# MAIN.net
KiCad netlist of a schematic drawn in Altium Designer
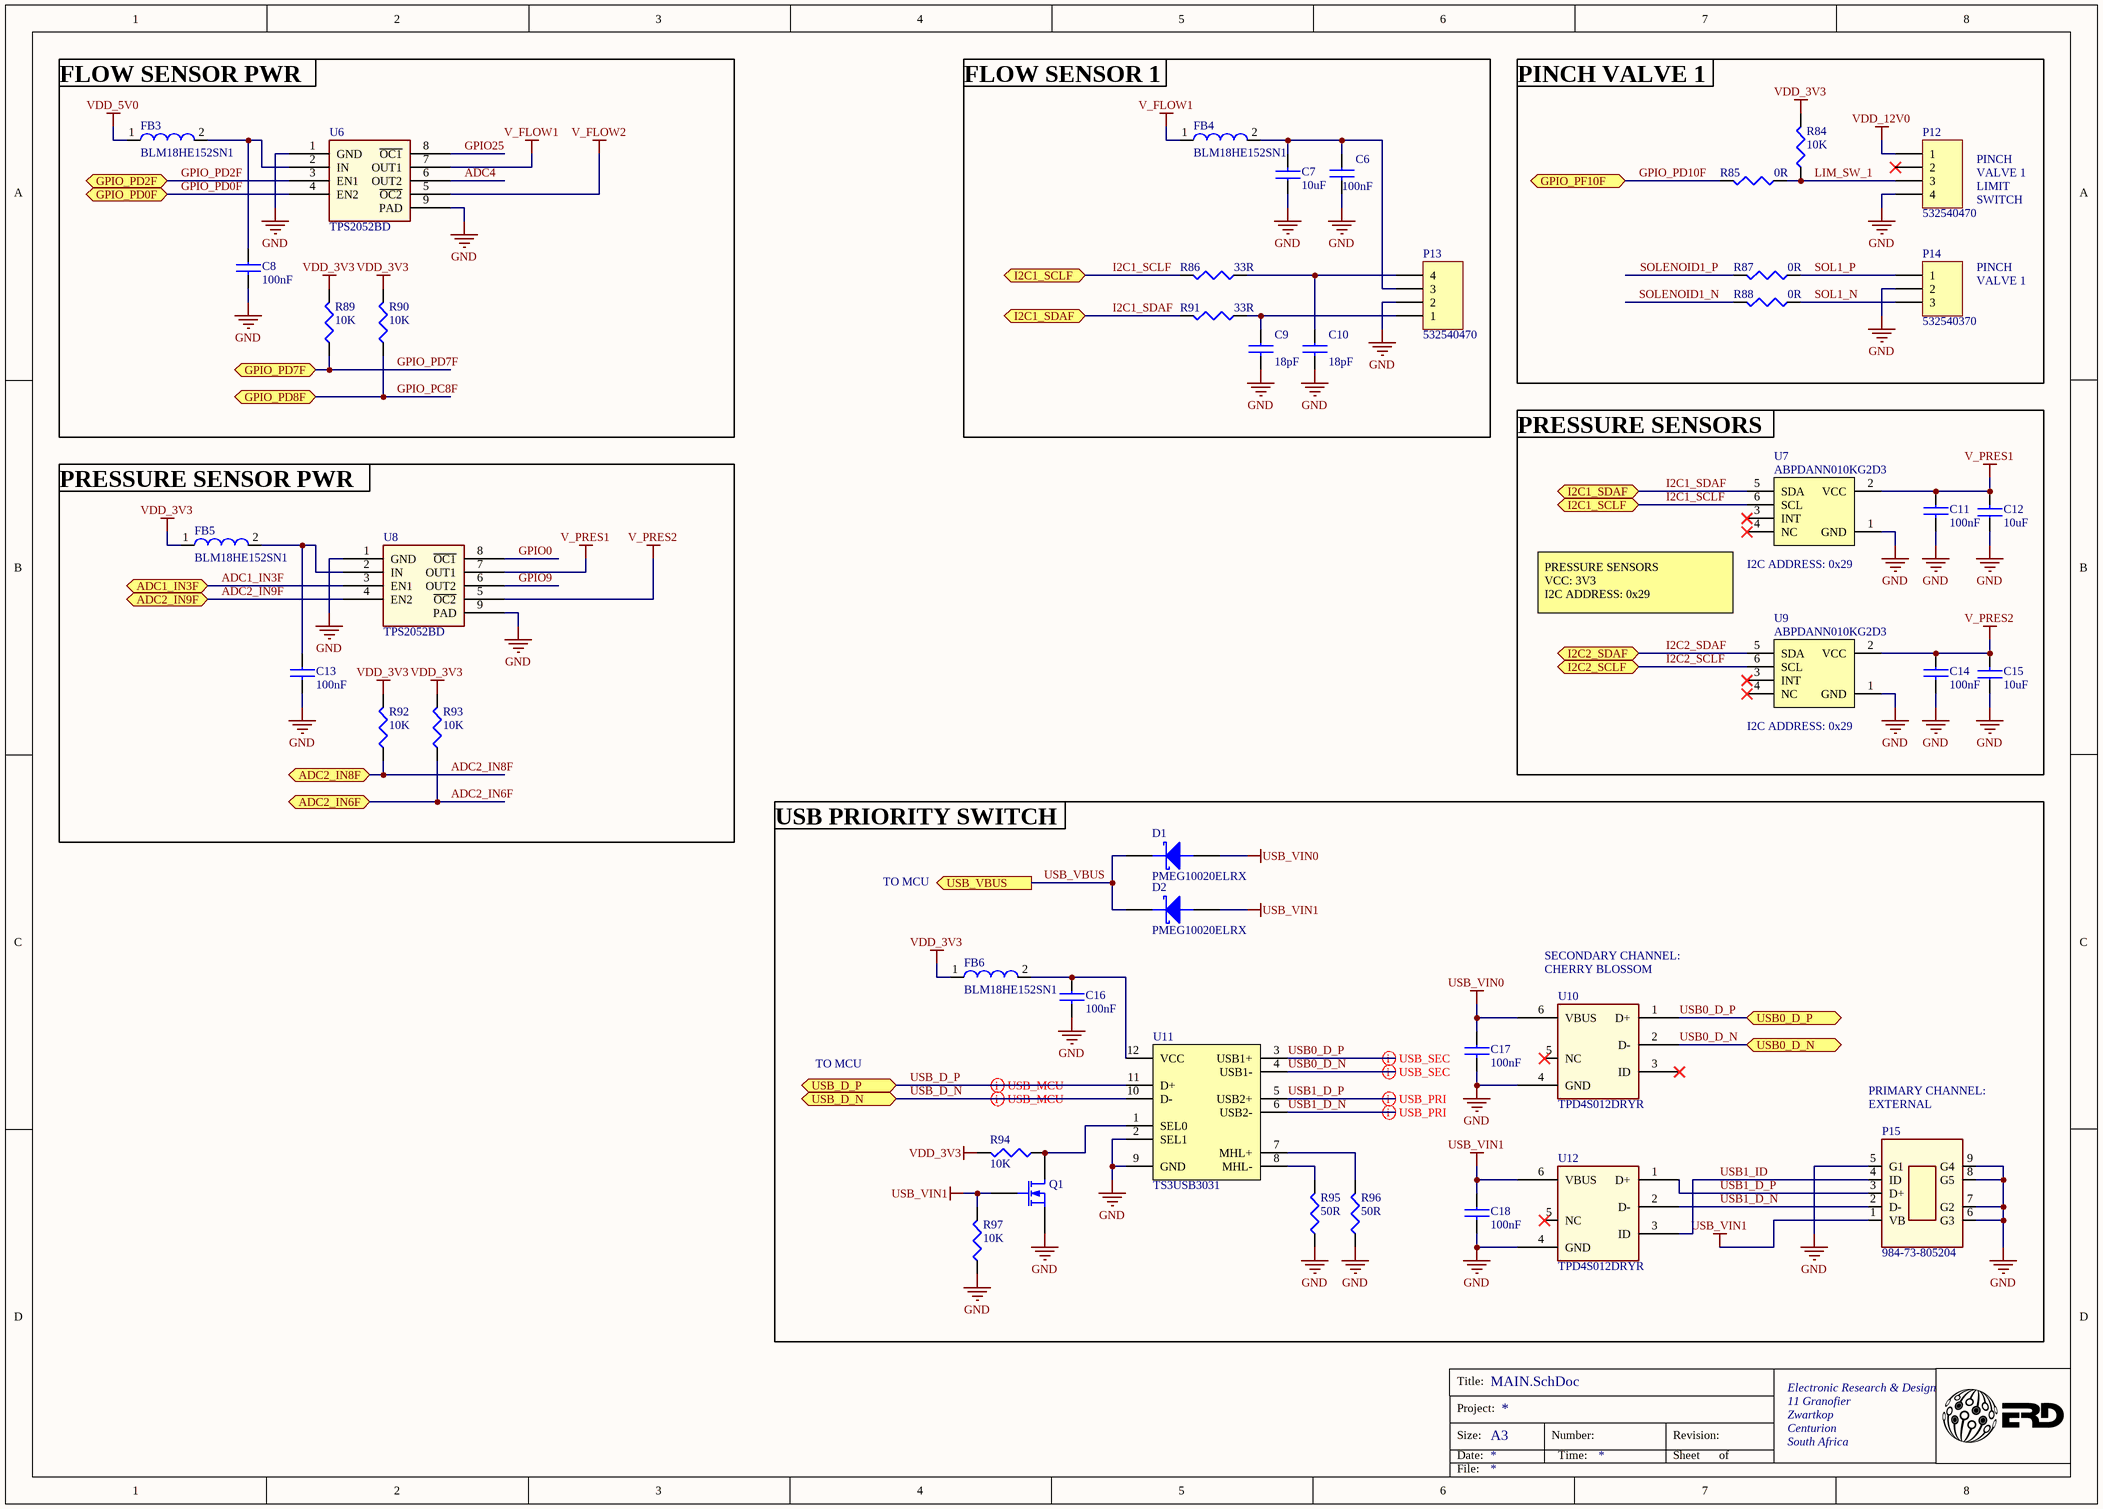
[diagram p0: MAIN.SchDoc]

(export (version "E")
  (design (tool "Eeschema 10.0.6"))
  (components
    (comp (ref "C6")
      (value "100nF")
      (footprint "CC0402")
      (description "CAP CER 0.1UF 50V 10% X7R 0402")
      (fields (field (name "MANUFACTURER") "Murata") (field (name "PART NUMBER") "GCM155R71H104KE02D"))
      (libsource (lib "ERD TiAm") (part "CAP CER 0.1UF 10V 10% X5R 0402"))
    )
    (comp (ref "C7")
      (value "10uF")
      (footprint "CC0603")
      (description "CAP CER 10UF 25V 20% X5R 0603")
      (fields (field (name "MANUFACTURER") "Murata") (field (name "PARTNUMBER") "GRM188R61E106MA73D"))
      (libsource (lib "ERD TiAm") (part "CAP CER 0.1UF 10V 10% X5R 0402"))
    )
    (comp (ref "C8")
      (value "100nF")
      (footprint "CC0402")
      (description "CAP CER 0.1UF 50V 10% X7R 0402")
      (fields (field (name "MANUFACTURER") "Murata") (field (name "PARTNUMBER") "GCM155R71H104KE02D"))
      (libsource (lib "ERD TiAm") (part "CAP CER 0.1UF 10V 10% X5R 0402"))
    )
    (comp (ref "C9")
      (value "18pF")
      (footprint "CC0402")
      (description "CAP CER 18pF 50V 5% C0G 0402")
      (fields (field (name "MANUFACTURER") "AVX") (field (name "PARTNUMBER") "GJM1555C1H180FB01D"))
      (libsource (lib "ERD TiAm") (part "CAP CER 2.2UF 6.3V 10% X5R 0402"))
    )
    (comp (ref "C10")
      (value "18pF")
      (footprint "CC0402")
      (description "CAP CER 18pF 50V 5% C0G 0402")
      (fields (field (name "MANUFACTURER") "AVX") (field (name "PARTNUMBER") "GJM1555C1H180FB01D"))
      (libsource (lib "ERD TiAm") (part "CAP CER 2.2UF 6.3V 10% X5R 0402"))
    )
    (comp (ref "C11")
      (value "100nF")
      (footprint "CC0402")
      (description "CAP CER 0.1UF 50V 10% X7R 0402")
      (fields (field (name "MANUFACTURER") "Murata") (field (name "PARTNUMBER") "GCM155R71H104KE02D"))
      (libsource (lib "ERD TiAm") (part "CAP CER 0.1UF 10V 10% X5R 0402"))
    )
    (comp (ref "C12")
      (value "10uF")
      (footprint "CC0603")
      (description "CAP CER 10UF 25V 20% X5R 0603")
      (fields (field (name "MANUFACTURER") "Murata") (field (name "PARTNUMBER") "GRM188R61E106MA73D"))
      (libsource (lib "ERD TiAm") (part "CAP CER 0.1UF 10V 10% X5R 0402"))
    )
    (comp (ref "C13")
      (value "100nF")
      (footprint "CC0402")
      (description "CAP CER 0.1UF 50V 10% X7R 0402")
      (fields (field (name "MANUFACTURER") "Murata") (field (name "PARTNUMBER") "GCM155R71H104KE02D"))
      (libsource (lib "ERD TiAm") (part "CAP CER 0.1UF 10V 10% X5R 0402"))
    )
    (comp (ref "C14")
      (value "100nF")
      (footprint "CC0402")
      (description "CAP CER 0.1UF 50V 10% X7R 0402")
      (fields (field (name "MANUFACTURER") "Murata") (field (name "PARTNUMBER") "GCM155R71H104KE02D"))
      (libsource (lib "ERD TiAm") (part "CAP CER 0.1UF 10V 10% X5R 0402"))
    )
    (comp (ref "C15")
      (value "10uF")
      (footprint "CC0603")
      (description "CAP CER 10UF 25V 20% X5R 0603")
      (fields (field (name "MANUFACTURER") "Murata") (field (name "PARTNUMBER") "GRM188R61E106MA73D"))
      (libsource (lib "ERD TiAm") (part "CAP CER 0.1UF 10V 10% X5R 0402"))
    )
    (comp (ref "C16")
      (value "100nF")
      (footprint "CC0402")
      (description "CAP CER 0.1UF 50V 10% X7R 0402")
      (fields (field (name "MANUFACTURER") "Murata") (field (name "PARTNUMBER") "GCM155R71H104KE02D"))
      (libsource (lib "ERD TiAm") (part "CAP CER 0.1UF 10V 10% X5R 0402"))
    )
    (comp (ref "C17")
      (value "100nF")
      (footprint "CC0402")
      (description "CAP CER 0.1UF 50V 10% X7R 0402")
      (fields (field (name "MANUFACTURER") "Murata") (field (name "PARTNUMBER") "GCM155R71H104KE02D"))
      (libsource (lib "ERD TiAm") (part "CAP CER 0.1UF 10V 10% X5R 0402"))
    )
    (comp (ref "C18")
      (value "100nF")
      (footprint "CC0402")
      (description "CAP CER 0.1UF 50V 10% X7R 0402")
      (fields (field (name "MANUFACTURER") "Murata") (field (name "PARTNUMBER") "GCM155R71H104KE02D"))
      (libsource (lib "ERD TiAm") (part "CAP CER 0.1UF 10V 10% X5R 0402"))
    )
    (comp (ref "D1")
      (value "PMEG10020ELRX")
      (footprint "SOD123W")
      (description "DIODE, SCHOTTKY, 100V, 2A, 3.7ns, SOD123W")
      (libsource (lib "GadgetJD") (part "DIODE SCHOTTKY"))
    )
    (comp (ref "D2")
      (value "PMEG10020ELRX")
      (footprint "SOD123W")
      (description "DIODE, SCHOTTKY, 100V, 2A, 3.7ns, SOD123W")
      (libsource (lib "GadgetJD") (part "DIODE SCHOTTKY"))
    )
    (comp (ref "FB3")
      (value "BLM18HE152SN1")
      (footprint "LC0603")
      (description "FERRITE, 500mA, 500mOHM, 0603")
      (libsource (lib "BEAGLEBONEBLACK_REV A5B") (part "FER_180_200_0"))
    )
    (comp (ref "FB4")
      (value "BLM18HE152SN1")
      (footprint "LC0603")
      (description "FERRITE, 500mA, 500mOHM, 0603")
      (libsource (lib "BEAGLEBONEBLACK_REV A5B") (part "FER_180_200_0"))
    )
    (comp (ref "FB5")
      (value "BLM18HE152SN1")
      (footprint "LC0603")
      (description "FERRITE, 500mA, 500mOHM, 0603")
      (libsource (lib "BEAGLEBONEBLACK_REV A5B") (part "FER_180_200_0"))
    )
    (comp (ref "FB6")
      (value "BLM18HE152SN1")
      (footprint "LC0603")
      (description "FERRITE, 500mA, 500mOHM, 0603")
      (libsource (lib "BEAGLEBONEBLACK_REV A5B") (part "FER_180_200_0"))
    )
    (comp (ref "P12")
      (value "532540470")
      (footprint "HDR1X4")
      (description "Header, RA, 4-circuit, 2mm pitch, TH")
      (fields (field (name "MANUFACTURER") "Molex"))
      (libsource (lib "") (part "Header 4_1"))
    )
    (comp (ref "P13")
      (value "532540470")
      (footprint "HDR1X4")
      (description "Header, RA, 4-circuit, 2mm pitch, TH")
      (fields (field (name "MANUFACTURER") "Molex"))
      (libsource (lib "Miscellaneous Connectors") (part "Header 4"))
    )
    (comp (ref "P14")
      (value "532540370")
      (footprint "HDR1X3")
      (description "Header, RA, 3-circuit, 2mm pitch, TH")
      (fields (field (name "MANUFACTURER") "Molex"))
      (libsource (lib "Miscellaneous Connectors") (part "Header 3"))
    )
    (comp (ref "P15")
      (value "984-73-805204")
      (footprint "984-73-805204")
      (description "CONN RCPT USB MICRO B R/A SMD")
      (fields (field (name "MANUFACTURER") "Pinrex"))
      (libsource (lib "ERD TiAm") (part "MINI-USB-AB-SOCKET"))
    )
    (comp (ref "Q1")
      (value "PMV45EN2R")
      (footprint "SOT23")
      (description "N-Channel FET, 20V, 1.5A, 140mOhm, SOT23")
      (fields (field (name "PUBLISHER") "Altium Limited"))
      (libsource (lib "Miscellaneous Devices") (part "MOSFET-N"))
    )
    (comp (ref "R84")
      (value "10K")
      (footprint "RC0402")
      (description "RES, 10K OHM, 1/16W, 1%, 0402")
      (fields (field (name "MANUFACTURER") "Yageo") (field (name "PART NUMBER") "RC0402FR-0710KL"))
      (libsource (lib "ERD TiAm") (part "RES_10K_1/16W_1%_0402"))
    )
    (comp (ref "R85")
      (value "0R")
      (footprint "RC0402")
      (description "RES, 0 OHM, 1/16W, 1%, 0402")
      (fields (field (name "MANUFACTURER") "Yageo") (field (name "PARTNUMBER") "RC0402FR-070RL"))
      (libsource (lib "ERD TiAm") (part "RES_10K_1/16W_1%_0402"))
    )
    (comp (ref "R86")
      (value "33R")
      (footprint "RC0402")
      (description "RES, 33 OHM, 1/16W, 1%, 0402")
      (fields (field (name "MANUFACTURER") "Yageo") (field (name "PARTNUMBER") "RC0402FR-0733RL"))
      (libsource (lib "ERD TiAm") (part "RES_10K_1/16W_1%_0402"))
    )
    (comp (ref "R87")
      (value "0R")
      (footprint "RC0402")
      (description "RES, 0 OHM, 1/16W, 1%, 0402")
      (fields (field (name "MANUFACTURER") "Yageo") (field (name "PARTNUMBER") "RC0402FR-070RL"))
      (libsource (lib "ERD TiAm") (part "RES_10K_1/16W_1%_0402"))
    )
    (comp (ref "R88")
      (value "0R")
      (footprint "RC0402")
      (description "RES, 0 OHM, 1/16W, 1%, 0402")
      (fields (field (name "MANUFACTURER") "Yageo") (field (name "PARTNUMBER") "RC0402FR-070RL"))
      (libsource (lib "ERD TiAm") (part "RES_10K_1/16W_1%_0402"))
    )
    (comp (ref "R89")
      (value "10K")
      (footprint "RC0402")
      (description "RES, 10K OHM, 1/16W, 1%, 0402")
      (fields (field (name "MANUFACTURER") "Yageo") (field (name "PARTNUMBER") "RC0402FR-0710KL"))
      (libsource (lib "ERD TiAm") (part "RES_10K_1/16W_1%_0402"))
    )
    (comp (ref "R90")
      (value "10K")
      (footprint "RC0402")
      (description "RES, 10K OHM, 1/16W, 1%, 0402")
      (fields (field (name "MANUFACTURER") "Yageo") (field (name "PARTNUMBER") "RC0402FR-0710KL"))
      (libsource (lib "ERD TiAm") (part "RES_10K_1/16W_1%_0402"))
    )
    (comp (ref "R91")
      (value "33R")
      (footprint "RC0402")
      (description "RES, 33 OHM, 1/16W, 1%, 0402")
      (fields (field (name "MANUFACTURER") "Yageo") (field (name "PARTNUMBER") "RC0402FR-0733RL"))
      (libsource (lib "ERD TiAm") (part "RES_10K_1/16W_1%_0402"))
    )
    (comp (ref "R92")
      (value "10K")
      (footprint "RC0402")
      (description "RES, 10K OHM, 1/16W, 1%, 0402")
      (fields (field (name "MANUFACTURER") "Yageo") (field (name "PARTNUMBER") "RC0402FR-0710KL"))
      (libsource (lib "ERD TiAm") (part "RES_10K_1/16W_1%_0402"))
    )
    (comp (ref "R93")
      (value "10K")
      (footprint "RC0402")
      (description "RES, 10K OHM, 1/16W, 1%, 0402")
      (fields (field (name "MANUFACTURER") "Yageo") (field (name "PARTNUMBER") "RC0402FR-0710KL"))
      (libsource (lib "ERD TiAm") (part "RES_10K_1/16W_1%_0402"))
    )
    (comp (ref "R94")
      (value "10K")
      (footprint "RC0402")
      (description "RES, 10K OHM, 1/16W, 1%, 0402")
      (fields (field (name "MANUFACTURER") "Yageo") (field (name "PARTNUMBER") "RC0402FR-0710KL"))
      (libsource (lib "ERD TiAm") (part "RES_10K_1/16W_1%_0402"))
    )
    (comp (ref "R95")
      (value "50R")
      (footprint "RC0402")
      (description "RES, 50 OHM, 1/16W, 1%, 0402")
      (fields (field (name "MANUFACTURER") "Yageo") (field (name "PARTNUMBER") "RC0402FR-0749R9L"))
      (libsource (lib "ERD TiAm") (part "RES_10K_1/16W_1%_0402"))
    )
    (comp (ref "R96")
      (value "50R")
      (footprint "RC0402")
      (description "RES, 50 OHM, 1/16W, 1%, 0402")
      (fields (field (name "MANUFACTURER") "Yageo") (field (name "PARTNUMBER") "RC0402FR-0749R9L"))
      (libsource (lib "ERD TiAm") (part "RES_10K_1/16W_1%_0402"))
    )
    (comp (ref "R97")
      (value "10K")
      (footprint "RC0402")
      (description "RES, 10K OHM, 1/16W, 1%, 0402")
      (fields (field (name "MANUFACTURER") "Yageo") (field (name "PARTNUMBER") "RC0402FR-0710KL"))
      (libsource (lib "ERD TiAm") (part "RES_10K_1/16W_1%_0402"))
    )
    (comp (ref "U6")
      (value "TPS2052BD")
      (description "IC 0.7A PWR DIST SWITCH 8-MSOP")
      (fields (field (name "ALTPARTNUMBER") "MP6231DH"))
      (libsource (lib "BaseBoard") (part "TPS2052"))
    )
    (comp (ref "U7")
      (value "ABPDANN010KG2D3")
      (description "Pressure Sensor, APB Series, TH")
      (libsource (lib "ERD TiAm") (part "ABPDANN010KG2D3"))
    )
    (comp (ref "U8")
      (value "TPS2052BD")
      (description "IC 0.7A PWR DIST SWITCH 8-MSOP")
      (fields (field (name "ALTPARTNUMBER") "MP6231DH"))
      (libsource (lib "BaseBoard") (part "TPS2052"))
    )
    (comp (ref "U9")
      (value "ABPDANN010KG2D3")
      (description "Pressure Sensor, APB Series, TH")
      (libsource (lib "ERD TiAm") (part "ABPDANN010KG2D3"))
    )
    (comp (ref "U10")
      (value "TPD4S012DRYR")
      (footprint "U_6_DRY")
      (description "ESD 4channel USB Interface")
      (fields (field (name "MANUFACTURER") "Texas Instruments"))
      (libsource (lib "ERD TiAm") (part "PROT_TPD4S012"))
    )
    (comp (ref "U11")
      (value "TS3USB3031")
      (description "USB Switch, USB 2.0, VQFN-12")
      (libsource (lib "ERD TiAm") (part "TS3USB3031"))
    )
    (comp (ref "U12")
      (value "TPD4S012DRYR")
      (footprint "U_6_DRY")
      (description "ESD 4channel USB Interface")
      (fields (field (name "MANUFACTURER") "Texas Instruments"))
      (libsource (lib "ERD TiAm") (part "PROT_TPD4S012"))
    )
  )
  (nets
    (net (code "1") (name "/ADC1_IN3F") (class "Default")
      (node (ref "U8") (pin "3") (pinfunction "EN1_3") (pintype "passive"))
    )
    (net (code "2") (name "/ADC2_IN6F") (class "Default")
      (node (ref "R93") (pin "1") (pinfunction "1_1") (pintype "passive"))
    )
    (net (code "3") (name "/ADC2_IN8F") (class "Default")
      (node (ref "R92") (pin "1") (pinfunction "1_1") (pintype "passive"))
    )
    (net (code "4") (name "/ADC2_IN9F") (class "Default")
      (node (ref "U8") (pin "4") (pinfunction "EN2_4") (pintype "passive"))
    )
    (net (code "5") (name "/ADC4") (class "Default")
      (node (ref "U6") (pin "6") (pinfunction "OUT2_6") (pintype "power_in"))
    )
    (net (code "6") (name "/GPIO0") (class "Default")
      (node (ref "U8") (pin "8") (pinfunction "~{OC1}_8") (pintype "power_in"))
    )
    (net (code "7") (name "/GPIO9") (class "Default")
      (node (ref "U8") (pin "6") (pinfunction "OUT2_6") (pintype "power_in"))
    )
    (net (code "8") (name "/GPIO25") (class "Default")
      (node (ref "U6") (pin "8") (pinfunction "~{OC1}_8") (pintype "power_in"))
    )
    (net (code "9") (name "/GPIO_PC8F") (class "Default")
      (node (ref "R90") (pin "1") (pinfunction "1_1") (pintype "passive"))
    )
    (net (code "10") (name "/GPIO_PD0F") (class "Default")
      (node (ref "U6") (pin "4") (pinfunction "EN2_4") (pintype "passive"))
    )
    (net (code "11") (name "/GPIO_PD2F") (class "Default")
      (node (ref "U6") (pin "3") (pinfunction "EN1_3") (pintype "passive"))
    )
    (net (code "12") (name "/GPIO_PD7F") (class "Default")
      (node (ref "R89") (pin "1") (pinfunction "1_1") (pintype "passive"))
    )
    (net (code "13") (name "/GPIO_PD10F") (class "Default")
      (node (ref "R85") (pin "2") (pinfunction "2_2") (pintype "passive"))
    )
    (net (code "14") (name "/I2C1_SCLF") (class "Default")
      (node (ref "R86") (pin "2") (pinfunction "2_2") (pintype "passive"))
      (node (ref "U7") (pin "6") (pinfunction "SCL_6") (pintype "passive"))
    )
    (net (code "15") (name "/I2C1_SDAF") (class "Default")
      (node (ref "R91") (pin "2") (pinfunction "2_2") (pintype "passive"))
      (node (ref "U7") (pin "5") (pinfunction "SDA_5") (pintype "passive"))
    )
    (net (code "16") (name "/I2C2_SCLF") (class "Default")
      (node (ref "U9") (pin "6") (pinfunction "SCL_6") (pintype "passive"))
    )
    (net (code "17") (name "/I2C2_SDAF") (class "Default")
      (node (ref "U9") (pin "5") (pinfunction "SDA_5") (pintype "passive"))
    )
    (net (code "18") (name "/LIM_SW_1") (class "Default")
      (node (ref "P12") (pin "3") (pinfunction "3_3") (pintype "passive"))
      (node (ref "R84") (pin "1") (pinfunction "1_1") (pintype "passive"))
      (node (ref "R85") (pin "1") (pinfunction "1_1") (pintype "passive"))
    )
    (net (code "19") (name "/SOL1_N") (class "Default")
      (node (ref "P14") (pin "3") (pinfunction "3_3") (pintype "passive"))
      (node (ref "R88") (pin "1") (pinfunction "1_1") (pintype "passive"))
    )
    (net (code "20") (name "/SOL1_P") (class "Default")
      (node (ref "P14") (pin "1") (pinfunction "1_1") (pintype "passive"))
      (node (ref "R87") (pin "1") (pinfunction "1_1") (pintype "passive"))
    )
    (net (code "21") (name "/SOLENOID1_N") (class "Default")
      (node (ref "R88") (pin "2") (pinfunction "2_2") (pintype "passive"))
    )
    (net (code "22") (name "/SOLENOID1_P") (class "Default")
      (node (ref "R87") (pin "2") (pinfunction "2_2") (pintype "passive"))
    )
    (net (code "23") (name "/USB0_D_N") (class "Default")
      (node (ref "U10") (pin "2") (pinfunction "D-_2") (pintype "passive"))
      (node (ref "U11") (pin "4") (pinfunction "USB1-_4") (pintype "passive"))
    )
    (net (code "24") (name "/USB0_D_P") (class "Default")
      (node (ref "U10") (pin "1") (pinfunction "D+_1") (pintype "passive"))
      (node (ref "U11") (pin "3") (pinfunction "USB1+_3") (pintype "passive"))
    )
    (net (code "25") (name "/USB1_D_N") (class "Default")
      (node (ref "P15") (pin "2") (pinfunction "D-_2") (pintype "passive"))
      (node (ref "U11") (pin "6") (pinfunction "USB2-_6") (pintype "passive"))
      (node (ref "U12") (pin "2") (pinfunction "D-_2") (pintype "passive"))
    )
    (net (code "26") (name "/USB1_D_P") (class "Default")
      (node (ref "P15") (pin "3") (pinfunction "D+_3") (pintype "passive"))
      (node (ref "U11") (pin "5") (pinfunction "USB2+_5") (pintype "passive"))
      (node (ref "U12") (pin "1") (pinfunction "D+_1") (pintype "passive"))
    )
    (net (code "27") (name "/USB1_ID") (class "Default")
      (node (ref "P15") (pin "4") (pinfunction "ID_4") (pintype "passive"))
      (node (ref "U12") (pin "3") (pinfunction "ID_3") (pintype "passive"))
    )
    (net (code "28") (name "/USB_D_N") (class "Default")
      (node (ref "U11") (pin "10") (pinfunction "D-_10") (pintype "passive"))
    )
    (net (code "29") (name "/USB_D_P") (class "Default")
      (node (ref "U11") (pin "11") (pinfunction "D+_11") (pintype "passive"))
    )
    (net (code "30") (name "/USB_VBUS") (class "Default")
      (node (ref "D1") (pin "1") (pinfunction "1_1") (pintype "passive"))
      (node (ref "D2") (pin "1") (pinfunction "1_1") (pintype "passive"))
    )
    (net (code "31") (name "GND") (class "Default")
      (node (ref "C10") (pin "2") (pinfunction "2_2") (pintype "passive"))
      (node (ref "C11") (pin "2") (pinfunction "2_2") (pintype "passive"))
      (node (ref "C12") (pin "1") (pinfunction "1_1") (pintype "passive"))
      (node (ref "C13") (pin "2") (pinfunction "2_2") (pintype "passive"))
      (node (ref "C14") (pin "2") (pinfunction "2_2") (pintype "passive"))
      (node (ref "C15") (pin "1") (pinfunction "1_1") (pintype "passive"))
      (node (ref "C16") (pin "2") (pinfunction "2_2") (pintype "passive"))
      (node (ref "C17") (pin "2") (pinfunction "2_2") (pintype "passive"))
      (node (ref "C18") (pin "2") (pinfunction "2_2") (pintype "passive"))
      (node (ref "C6") (pin "2") (pinfunction "2_2") (pintype "passive"))
      (node (ref "C7") (pin "1") (pinfunction "1_1") (pintype "passive"))
      (node (ref "C8") (pin "2") (pinfunction "2_2") (pintype "passive"))
      (node (ref "C9") (pin "2") (pinfunction "2_2") (pintype "passive"))
      (node (ref "P12") (pin "4") (pinfunction "4_4") (pintype "passive"))
      (node (ref "P13") (pin "2") (pinfunction "2_2") (pintype "passive"))
      (node (ref "P14") (pin "2") (pinfunction "2_2") (pintype "passive"))
      (node (ref "P15") (pin "5") (pinfunction "G1_5") (pintype "passive"))
      (node (ref "P15") (pin "6") (pinfunction "G3_6") (pintype "passive"))
      (node (ref "P15") (pin "7") (pinfunction "G2_7") (pintype "passive"))
      (node (ref "P15") (pin "8") (pinfunction "G5_8") (pintype "passive"))
      (node (ref "P15") (pin "9") (pinfunction "G4_9") (pintype "passive"))
      (node (ref "Q1") (pin "3") (pinfunction "S_3") (pintype "passive"))
      (node (ref "R95") (pin "1") (pinfunction "1_1") (pintype "passive"))
      (node (ref "R96") (pin "1") (pinfunction "1_1") (pintype "passive"))
      (node (ref "R97") (pin "1") (pinfunction "1_1") (pintype "passive"))
      (node (ref "U10") (pin "4") (pinfunction "GND_4") (pintype "power_in"))
      (node (ref "U11") (pin "2") (pinfunction "SEL1_2") (pintype "passive"))
      (node (ref "U11") (pin "9") (pinfunction "GND_9") (pintype "passive"))
      (node (ref "U12") (pin "4") (pinfunction "GND_4") (pintype "power_in"))
      (node (ref "U6") (pin "1") (pinfunction "GND_1") (pintype "power_in"))
      (node (ref "U6") (pin "9") (pinfunction "PAD_9") (pintype "passive"))
      (node (ref "U7") (pin "1") (pinfunction "GND_1") (pintype "passive"))
      (node (ref "U8") (pin "1") (pinfunction "GND_1") (pintype "power_in"))
      (node (ref "U8") (pin "9") (pinfunction "PAD_9") (pintype "passive"))
      (node (ref "U9") (pin "1") (pinfunction "GND_1") (pintype "passive"))
    )
    (net (code "32") (name "Net-(C6-Pad1)") (class "Default")
      (node (ref "C6") (pin "1") (pinfunction "1_1") (pintype "passive"))
      (node (ref "C7") (pin "2") (pinfunction "2_2") (pintype "passive"))
      (node (ref "FB4") (pin "2") (pinfunction "2_2") (pintype "passive"))
      (node (ref "P13") (pin "3") (pinfunction "3_3") (pintype "passive"))
    )
    (net (code "33") (name "Net-(C9-Pad1)") (class "Default")
      (node (ref "C9") (pin "1") (pinfunction "1_1") (pintype "passive"))
      (node (ref "P13") (pin "1") (pinfunction "1_1") (pintype "passive"))
      (node (ref "R91") (pin "1") (pinfunction "1_1") (pintype "passive"))
    )
    (net (code "34") (name "Net-(C10-Pad1)") (class "Default")
      (node (ref "C10") (pin "1") (pinfunction "1_1") (pintype "passive"))
      (node (ref "P13") (pin "4") (pinfunction "4_4") (pintype "passive"))
      (node (ref "R86") (pin "1") (pinfunction "1_1") (pintype "passive"))
    )
    (net (code "35") (name "Net-(Q1-D)") (class "Default")
      (node (ref "Q1") (pin "1") (pinfunction "D_1") (pintype "passive"))
      (node (ref "R94") (pin "1") (pinfunction "1_1") (pintype "passive"))
      (node (ref "U11") (pin "1") (pinfunction "SEL0_1") (pintype "passive"))
    )
    (net (code "36") (name "Net-(U6-IN)") (class "Default")
      (node (ref "C8") (pin "1") (pinfunction "1_1") (pintype "passive"))
      (node (ref "FB3") (pin "2") (pinfunction "2_2") (pintype "passive"))
      (node (ref "U6") (pin "2") (pinfunction "IN_2") (pintype "power_in"))
    )
    (net (code "37") (name "Net-(U8-IN)") (class "Default")
      (node (ref "C13") (pin "1") (pinfunction "1_1") (pintype "passive"))
      (node (ref "FB5") (pin "2") (pinfunction "2_2") (pintype "passive"))
      (node (ref "U8") (pin "2") (pinfunction "IN_2") (pintype "power_in"))
    )
    (net (code "38") (name "Net-(U11-MHL+)") (class "Default")
      (node (ref "R96") (pin "2") (pinfunction "2_2") (pintype "passive"))
      (node (ref "U11") (pin "7") (pinfunction "MHL+_7") (pintype "passive"))
    )
    (net (code "39") (name "Net-(U11-MHL-)") (class "Default")
      (node (ref "R95") (pin "2") (pinfunction "2_2") (pintype "passive"))
      (node (ref "U11") (pin "8") (pinfunction "MHL-_8") (pintype "passive"))
    )
    (net (code "40") (name "Net-(U11-VCC)") (class "Default")
      (node (ref "C16") (pin "1") (pinfunction "1_1") (pintype "passive"))
      (node (ref "FB6") (pin "2") (pinfunction "2_2") (pintype "passive"))
      (node (ref "U11") (pin "12") (pinfunction "VCC_12") (pintype "passive"))
    )
    (net (code "41") (name "USB_VIN0") (class "Default")
      (node (ref "C17") (pin "1") (pinfunction "1_1") (pintype "passive"))
      (node (ref "D1") (pin "2") (pinfunction "2_2") (pintype "passive"))
      (node (ref "U10") (pin "6") (pinfunction "VBUS_6") (pintype "power_in"))
    )
    (net (code "42") (name "USB_VIN1") (class "Default")
      (node (ref "C18") (pin "1") (pinfunction "1_1") (pintype "passive"))
      (node (ref "D2") (pin "2") (pinfunction "2_2") (pintype "passive"))
      (node (ref "P15") (pin "1") (pinfunction "VB_1") (pintype "passive"))
      (node (ref "Q1") (pin "2") (pinfunction "G_2") (pintype "passive"))
      (node (ref "R97") (pin "2") (pinfunction "2_2") (pintype "passive"))
      (node (ref "U12") (pin "6") (pinfunction "VBUS_6") (pintype "power_in"))
    )
    (net (code "43") (name "VDD_3V3") (class "Default")
      (node (ref "FB5") (pin "1") (pinfunction "1_1") (pintype "passive"))
      (node (ref "FB6") (pin "1") (pinfunction "1_1") (pintype "passive"))
      (node (ref "R84") (pin "2") (pinfunction "2_2") (pintype "passive"))
      (node (ref "R89") (pin "2") (pinfunction "2_2") (pintype "passive"))
      (node (ref "R90") (pin "2") (pinfunction "2_2") (pintype "passive"))
      (node (ref "R92") (pin "2") (pinfunction "2_2") (pintype "passive"))
      (node (ref "R93") (pin "2") (pinfunction "2_2") (pintype "passive"))
      (node (ref "R94") (pin "2") (pinfunction "2_2") (pintype "passive"))
    )
    (net (code "44") (name "VDD_5V0") (class "Default")
      (node (ref "FB3") (pin "1") (pinfunction "1_1") (pintype "passive"))
    )
    (net (code "45") (name "VDD_12V0") (class "Default")
      (node (ref "P12") (pin "1") (pinfunction "1_1") (pintype "passive"))
    )
    (net (code "46") (name "V_FLOW1") (class "Default")
      (node (ref "FB4") (pin "1") (pinfunction "1_1") (pintype "passive"))
      (node (ref "U6") (pin "7") (pinfunction "OUT1_7") (pintype "power_in"))
    )
    (net (code "47") (name "V_FLOW2") (class "Default")
      (node (ref "U6") (pin "5") (pinfunction "~{OC2}_5") (pintype "passive"))
    )
    (net (code "48") (name "V_PRES1") (class "Default")
      (node (ref "C11") (pin "1") (pinfunction "1_1") (pintype "passive"))
      (node (ref "C12") (pin "2") (pinfunction "2_2") (pintype "passive"))
      (node (ref "U7") (pin "2") (pinfunction "VCC_2") (pintype "passive"))
      (node (ref "U8") (pin "7") (pinfunction "OUT1_7") (pintype "power_in"))
    )
    (net (code "49") (name "V_PRES2") (class "Default")
      (node (ref "C14") (pin "1") (pinfunction "1_1") (pintype "passive"))
      (node (ref "C15") (pin "2") (pinfunction "2_2") (pintype "passive"))
      (node (ref "U8") (pin "5") (pinfunction "~{OC2}_5") (pintype "passive"))
      (node (ref "U9") (pin "2") (pinfunction "VCC_2") (pintype "passive"))
    )
    (net (code "50") (name "unconnected-(P12-Pad2)") (class "Default")
      (node (ref "P12") (pin "2") (pinfunction "2_2") (pintype "passive+no_connect"))
    )
    (net (code "51") (name "unconnected-(U7-INT-Pad3)") (class "Default")
      (node (ref "U7") (pin "3") (pinfunction "INT_3") (pintype "passive+no_connect"))
    )
    (net (code "52") (name "unconnected-(U7-NC-Pad4)") (class "Default")
      (node (ref "U7") (pin "4") (pinfunction "NC_4") (pintype "passive+no_connect"))
    )
    (net (code "53") (name "unconnected-(U9-INT-Pad3)") (class "Default")
      (node (ref "U9") (pin "3") (pinfunction "INT_3") (pintype "passive+no_connect"))
    )
    (net (code "54") (name "unconnected-(U9-NC-Pad4)") (class "Default")
      (node (ref "U9") (pin "4") (pinfunction "NC_4") (pintype "passive+no_connect"))
    )
    (net (code "55") (name "unconnected-(U10-ID-Pad3)") (class "Default")
      (node (ref "U10") (pin "3") (pinfunction "ID_3") (pintype "passive+no_connect"))
    )
    (net (code "56") (name "unconnected-(U10-NC-Pad5)") (class "Default")
      (node (ref "U10") (pin "5") (pinfunction "NC_5") (pintype "passive+no_connect"))
    )
    (net (code "57") (name "unconnected-(U12-NC-Pad5)") (class "Default")
      (node (ref "U12") (pin "5") (pinfunction "NC_5") (pintype "passive+no_connect"))
    )
  )
)
